# clock.net
KiCad netlist of a schematic drawn in EAGLE
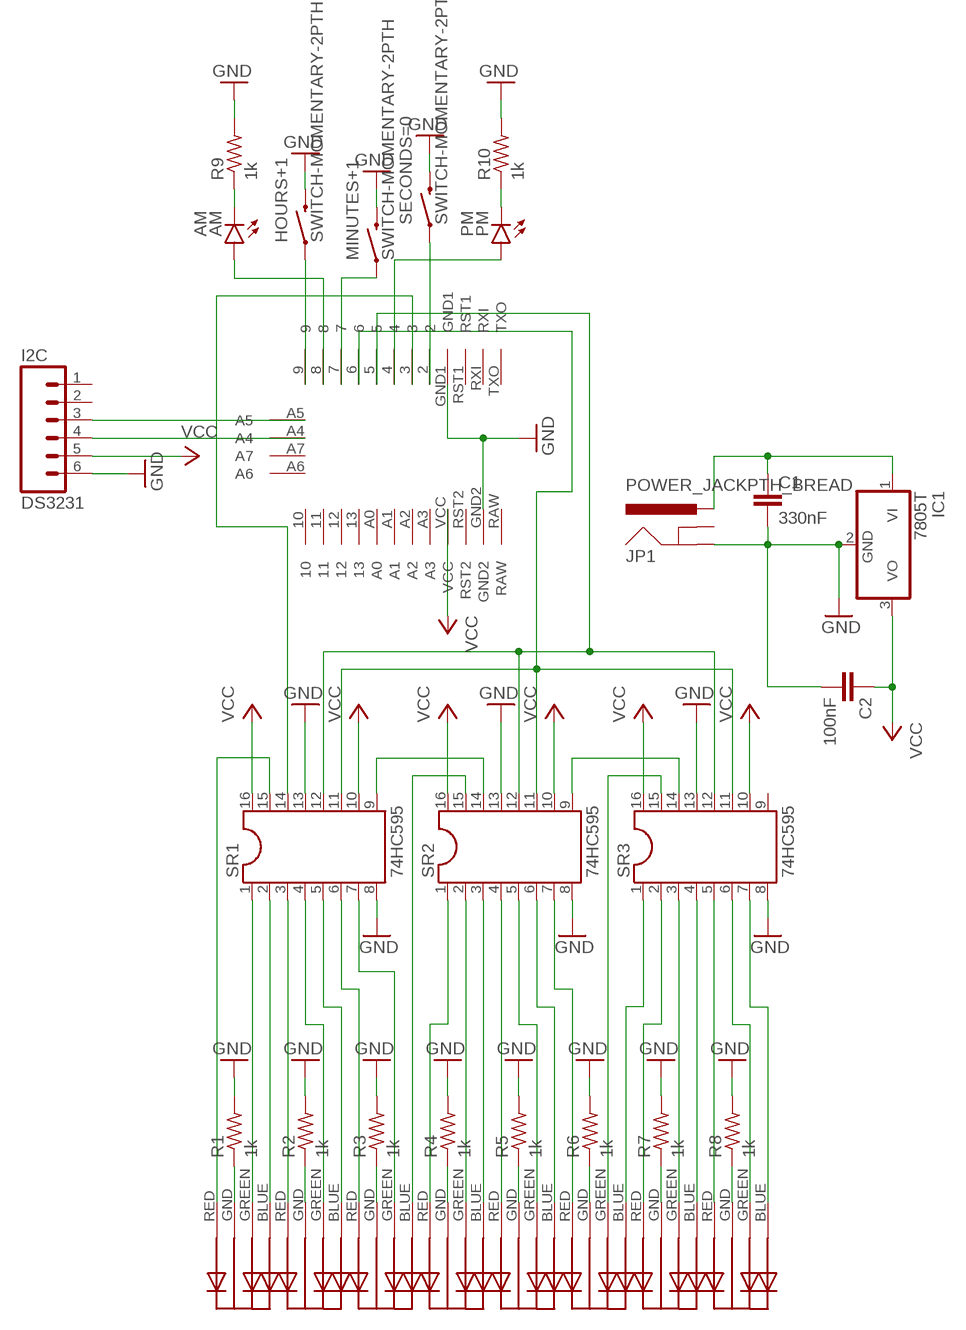
[diagram p0: schematic, sheet 1]

(export (version "E")
  (design (tool "Eeschema 10.0.6"))
  (components
    (comp (ref "AM")
      (value "AM")
      (footprint "eagle-import:LED5MM")
      (libsource (lib "eagle-import") (part "LED5MM"))
    )
    (comp (ref "C1")
      (value "330nF")
      (footprint "eagle-import:CAP-PTH-5MM")
      (libsource (lib "eagle-import") (part "CAPPTH1"))
    )
    (comp (ref "C2")
      (value "100nF")
      (footprint "eagle-import:CAP-PTH-5MM")
      (libsource (lib "eagle-import") (part "CAPPTH1"))
    )
    (comp (ref "DS3231")
      (value "I2C")
      (footprint "eagle-import:1X06_LOCK")
      (libsource (lib "eagle-import") (part "M06LOCK"))
    )
    (comp (ref "HOURS+1")
      (value "SWITCH-MOMENTARY-2PTH")
      (footprint "eagle-import:TACTILE-PTH")
      (libsource (lib "eagle-import") (part "SWITCH-MOMENTARY-2PTH"))
    )
    (comp (ref "IC1")
      (value "7805T")
      (footprint "eagle-import:TO220V")
      (libsource (lib "eagle-import") (part "78TV05"))
    )
    (comp (ref "JP1")
      (value "POWER_JACKPTH_BREAD")
      (footprint "eagle-import:POWER_JACK_PTH_BREAD")
      (libsource (lib "eagle-import") (part "POWER_JACKPTH_BREAD"))
    )
    (comp (ref "MINUTES+1")
      (value "SWITCH-MOMENTARY-2PTH")
      (footprint "eagle-import:TACTILE-PTH")
      (libsource (lib "eagle-import") (part "SWITCH-MOMENTARY-2PTH"))
    )
    (comp (ref "PM")
      (value "PM")
      (footprint "eagle-import:LED5MM")
      (libsource (lib "eagle-import") (part "LED5MM"))
    )
    (comp (ref "R1")
      (value "1k")
      (footprint "eagle-import:0207_10")
      (libsource (lib "eagle-import") (part "R-US_0207/10"))
    )
    (comp (ref "R2")
      (value "1k")
      (footprint "eagle-import:0207_10")
      (libsource (lib "eagle-import") (part "R-US_0207/10"))
    )
    (comp (ref "R3")
      (value "1k")
      (footprint "eagle-import:0207_10")
      (libsource (lib "eagle-import") (part "R-US_0207/10"))
    )
    (comp (ref "R4")
      (value "1k")
      (footprint "eagle-import:0207_10")
      (libsource (lib "eagle-import") (part "R-US_0207/10"))
    )
    (comp (ref "R5")
      (value "1k")
      (footprint "eagle-import:0207_10")
      (libsource (lib "eagle-import") (part "R-US_0207/10"))
    )
    (comp (ref "R6")
      (value "1k")
      (footprint "eagle-import:0207_10")
      (libsource (lib "eagle-import") (part "R-US_0207/10"))
    )
    (comp (ref "R7")
      (value "1k")
      (footprint "eagle-import:0207_10")
      (libsource (lib "eagle-import") (part "R-US_0207/10"))
    )
    (comp (ref "R8")
      (value "1k")
      (footprint "eagle-import:0207_10")
      (libsource (lib "eagle-import") (part "R-US_0207/10"))
    )
    (comp (ref "R9")
      (value "1k")
      (footprint "eagle-import:0207_10")
      (libsource (lib "eagle-import") (part "R-US_0207/10"))
    )
    (comp (ref "R10")
      (value "1k")
      (footprint "eagle-import:0207_10")
      (libsource (lib "eagle-import") (part "R-US_0207/10"))
    )
    (comp (ref "SECONDS=0")
      (value "SWITCH-MOMENTARY-2PTH")
      (footprint "eagle-import:TACTILE-PTH")
      (libsource (lib "eagle-import") (part "SWITCH-MOMENTARY-2PTH"))
    )
    (comp (ref "SR1")
      (value "74HC595")
      (footprint "eagle-import:SOCKET-16")
      (libsource (lib "eagle-import") (part "DIL16S"))
    )
    (comp (ref "SR2")
      (value "74HC595")
      (footprint "eagle-import:SOCKET-16")
      (libsource (lib "eagle-import") (part "DIL16S"))
    )
    (comp (ref "SR3")
      (value "74HC595")
      (footprint "eagle-import:SOCKET-16")
      (libsource (lib "eagle-import") (part "DIL16S"))
    )
    (comp (ref "U$1")
      (value "PRO-MINI")
      (footprint "eagle-import:PRO-MINI")
      (libsource (lib "eagle-import") (part "PRO-MINI"))
    )
    (comp (ref "U$2")
      (value "RGB_LED_COM_CATH")
      (footprint "eagle-import:RGB_LED_COM_CATH")
      (libsource (lib "eagle-import") (part "RGB_LED_COM_CATH"))
    )
    (comp (ref "U$3")
      (value "RGB_LED_COM_CATH")
      (footprint "eagle-import:RGB_LED_COM_CATH")
      (libsource (lib "eagle-import") (part "RGB_LED_COM_CATH"))
    )
    (comp (ref "U$4")
      (value "RGB_LED_COM_CATH")
      (footprint "eagle-import:RGB_LED_COM_CATH")
      (libsource (lib "eagle-import") (part "RGB_LED_COM_CATH"))
    )
    (comp (ref "U$5")
      (value "RGB_LED_COM_CATH")
      (footprint "eagle-import:RGB_LED_COM_CATH")
      (libsource (lib "eagle-import") (part "RGB_LED_COM_CATH"))
    )
    (comp (ref "U$6")
      (value "RGB_LED_COM_CATH")
      (footprint "eagle-import:RGB_LED_COM_CATH")
      (libsource (lib "eagle-import") (part "RGB_LED_COM_CATH"))
    )
    (comp (ref "U$7")
      (value "RGB_LED_COM_CATH")
      (footprint "eagle-import:RGB_LED_COM_CATH")
      (libsource (lib "eagle-import") (part "RGB_LED_COM_CATH"))
    )
    (comp (ref "U$8")
      (value "RGB_LED_COM_CATH")
      (footprint "eagle-import:RGB_LED_COM_CATH")
      (libsource (lib "eagle-import") (part "RGB_LED_COM_CATH"))
    )
    (comp (ref "U$9")
      (value "RGB_LED_COM_CATH")
      (footprint "eagle-import:RGB_LED_COM_CATH")
      (libsource (lib "eagle-import") (part "RGB_LED_COM_CATH"))
    )
  )
  (nets
    (net (code "1") (name "GND") (class "Default")
      (node (ref "C1") (pin "2") (pinfunction "2_2") (pintype "passive"))
      (node (ref "C2") (pin "2") (pinfunction "2_2") (pintype "passive"))
      (node (ref "DS3231") (pin "6") (pinfunction "6_6") (pintype "passive"))
      (node (ref "HOURS+1") (pin "3") (pinfunction "2_3") (pintype "passive"))
      (node (ref "IC1") (pin "2") (pinfunction "GND_2") (pintype "passive"))
      (node (ref "JP1") (pin "GND") (pinfunction "GND_GND") (pintype "bidirectional"))
      (node (ref "MINUTES+1") (pin "3") (pinfunction "2_3") (pintype "passive"))
      (node (ref "R1") (pin "2") (pinfunction "2_2") (pintype "passive"))
      (node (ref "R10") (pin "2") (pinfunction "2_2") (pintype "passive"))
      (node (ref "R2") (pin "2") (pinfunction "2_2") (pintype "passive"))
      (node (ref "R3") (pin "2") (pinfunction "2_2") (pintype "passive"))
      (node (ref "R4") (pin "2") (pinfunction "2_2") (pintype "passive"))
      (node (ref "R5") (pin "2") (pinfunction "2_2") (pintype "passive"))
      (node (ref "R6") (pin "2") (pinfunction "2_2") (pintype "passive"))
      (node (ref "R7") (pin "2") (pinfunction "2_2") (pintype "passive"))
      (node (ref "R8") (pin "2") (pinfunction "2_2") (pintype "passive"))
      (node (ref "R9") (pin "2") (pinfunction "2_2") (pintype "passive"))
      (node (ref "SECONDS=0") (pin "3") (pinfunction "2_3") (pintype "passive"))
      (node (ref "SR1") (pin "13") (pinfunction "13_13") (pintype "passive"))
      (node (ref "SR1") (pin "8") (pinfunction "8_8") (pintype "passive"))
      (node (ref "SR2") (pin "13") (pinfunction "13_13") (pintype "passive"))
      (node (ref "SR2") (pin "8") (pinfunction "8_8") (pintype "passive"))
      (node (ref "SR3") (pin "13") (pinfunction "13_13") (pintype "passive"))
      (node (ref "SR3") (pin "8") (pinfunction "8_8") (pintype "passive"))
      (node (ref "U$1") (pin "GND1") (pinfunction "GND1_GND1") (pintype "bidirectional"))
      (node (ref "U$1") (pin "GND2") (pinfunction "GND2_GND2") (pintype "bidirectional"))
    )
    (net (code "2") (name "Net-(AM-C)") (class "Default")
      (node (ref "AM") (pin "K") (pinfunction "C_K") (pintype "passive"))
      (node (ref "R9") (pin "1") (pinfunction "1_1") (pintype "passive"))
    )
    (net (code "3") (name "Net-(AM-PadA)") (class "Default")
      (node (ref "AM") (pin "A") (pinfunction "A_A") (pintype "passive"))
      (node (ref "U$1") (pin "8") (pinfunction "8_8") (pintype "bidirectional"))
    )
    (net (code "4") (name "Net-(DS3231-Pad3)") (class "Default")
      (node (ref "DS3231") (pin "3") (pinfunction "3_3") (pintype "passive"))
      (node (ref "U$1") (pin "A5") (pinfunction "A5_A5") (pintype "bidirectional"))
    )
    (net (code "5") (name "Net-(DS3231-Pad4)") (class "Default")
      (node (ref "DS3231") (pin "4") (pinfunction "4_4") (pintype "passive"))
      (node (ref "U$1") (pin "A4") (pinfunction "A4_A4") (pintype "bidirectional"))
    )
    (net (code "6") (name "Net-(HOURS+1-Pad1)") (class "Default")
      (node (ref "HOURS+1") (pin "1") (pinfunction "1_1") (pintype "passive"))
      (node (ref "U$1") (pin "9") (pinfunction "9_9") (pintype "bidirectional"))
    )
    (net (code "7") (name "Net-(IC1-VI)") (class "Default")
      (node (ref "C1") (pin "1") (pinfunction "1_1") (pintype "passive"))
      (node (ref "IC1") (pin "1") (pinfunction "VI_1") (pintype "input"))
      (node (ref "JP1") (pin "PWR") (pinfunction "PWR_PWR") (pintype "bidirectional"))
    )
    (net (code "8") (name "Net-(MINUTES+1-Pad1)") (class "Default")
      (node (ref "MINUTES+1") (pin "1") (pinfunction "1_1") (pintype "passive"))
      (node (ref "U$1") (pin "7") (pinfunction "7_7") (pintype "bidirectional"))
    )
    (net (code "9") (name "Net-(PM-C)") (class "Default")
      (node (ref "PM") (pin "K") (pinfunction "C_K") (pintype "passive"))
      (node (ref "R10") (pin "1") (pinfunction "1_1") (pintype "passive"))
    )
    (net (code "10") (name "Net-(PM-PadA)") (class "Default")
      (node (ref "PM") (pin "A") (pinfunction "A_A") (pintype "passive"))
      (node (ref "U$1") (pin "4") (pinfunction "4_4") (pintype "bidirectional"))
    )
    (net (code "11") (name "Net-(R1-Pad1)") (class "Default")
      (node (ref "R1") (pin "1") (pinfunction "1_1") (pintype "passive"))
      (node (ref "U$4") (pin "GND") (pinfunction "GND_GND") (pintype "bidirectional"))
    )
    (net (code "12") (name "Net-(R2-Pad1)") (class "Default")
      (node (ref "R2") (pin "1") (pinfunction "1_1") (pintype "passive"))
      (node (ref "U$3") (pin "GND") (pinfunction "GND_GND") (pintype "bidirectional"))
    )
    (net (code "13") (name "Net-(R3-Pad1)") (class "Default")
      (node (ref "R3") (pin "1") (pinfunction "1_1") (pintype "passive"))
      (node (ref "U$2") (pin "GND") (pinfunction "GND_GND") (pintype "bidirectional"))
    )
    (net (code "14") (name "Net-(R4-Pad1)") (class "Default")
      (node (ref "R4") (pin "1") (pinfunction "1_1") (pintype "passive"))
      (node (ref "U$5") (pin "GND") (pinfunction "GND_GND") (pintype "bidirectional"))
    )
    (net (code "15") (name "Net-(R5-Pad1)") (class "Default")
      (node (ref "R5") (pin "1") (pinfunction "1_1") (pintype "passive"))
      (node (ref "U$6") (pin "GND") (pinfunction "GND_GND") (pintype "bidirectional"))
    )
    (net (code "16") (name "Net-(R6-Pad1)") (class "Default")
      (node (ref "R6") (pin "1") (pinfunction "1_1") (pintype "passive"))
      (node (ref "U$7") (pin "GND") (pinfunction "GND_GND") (pintype "bidirectional"))
    )
    (net (code "17") (name "Net-(R7-Pad1)") (class "Default")
      (node (ref "R7") (pin "1") (pinfunction "1_1") (pintype "passive"))
      (node (ref "U$8") (pin "GND") (pinfunction "GND_GND") (pintype "bidirectional"))
    )
    (net (code "18") (name "Net-(R8-Pad1)") (class "Default")
      (node (ref "R8") (pin "1") (pinfunction "1_1") (pintype "passive"))
      (node (ref "U$9") (pin "GND") (pinfunction "GND_GND") (pintype "bidirectional"))
    )
    (net (code "19") (name "Net-(SECONDS=0-Pad1)") (class "Default")
      (node (ref "SECONDS=0") (pin "1") (pinfunction "1_1") (pintype "passive"))
      (node (ref "U$1") (pin "2") (pinfunction "2_2") (pintype "bidirectional"))
    )
    (net (code "20") (name "Net-(SR1-Pad1)") (class "Default")
      (node (ref "SR1") (pin "1") (pinfunction "1_1") (pintype "passive"))
      (node (ref "U$4") (pin "GREEN") (pinfunction "GREEN_GREEN") (pintype "bidirectional"))
    )
    (net (code "21") (name "Net-(SR1-Pad2)") (class "Default")
      (node (ref "SR1") (pin "2") (pinfunction "2_2") (pintype "passive"))
      (node (ref "U$4") (pin "BLUE") (pinfunction "BLUE_BLUE") (pintype "bidirectional"))
    )
    (net (code "22") (name "Net-(SR1-Pad3)") (class "Default")
      (node (ref "SR1") (pin "3") (pinfunction "3_3") (pintype "passive"))
      (node (ref "U$3") (pin "RED") (pinfunction "RED_RED") (pintype "bidirectional"))
    )
    (net (code "23") (name "Net-(SR1-Pad4)") (class "Default")
      (node (ref "SR1") (pin "4") (pinfunction "4_4") (pintype "passive"))
      (node (ref "U$3") (pin "GREEN") (pinfunction "GREEN_GREEN") (pintype "bidirectional"))
    )
    (net (code "24") (name "Net-(SR1-Pad5)") (class "Default")
      (node (ref "SR1") (pin "5") (pinfunction "5_5") (pintype "passive"))
      (node (ref "U$3") (pin "BLUE") (pinfunction "BLUE_BLUE") (pintype "bidirectional"))
    )
    (net (code "25") (name "Net-(SR1-Pad6)") (class "Default")
      (node (ref "SR1") (pin "6") (pinfunction "6_6") (pintype "passive"))
      (node (ref "U$2") (pin "RED") (pinfunction "RED_RED") (pintype "bidirectional"))
    )
    (net (code "26") (name "Net-(SR1-Pad7)") (class "Default")
      (node (ref "SR1") (pin "7") (pinfunction "7_7") (pintype "passive"))
      (node (ref "U$2") (pin "GREEN") (pinfunction "GREEN_GREEN") (pintype "bidirectional"))
    )
    (net (code "27") (name "Net-(SR1-Pad9)") (class "Default")
      (node (ref "SR1") (pin "9") (pinfunction "9_9") (pintype "passive"))
      (node (ref "SR2") (pin "14") (pinfunction "14_14") (pintype "passive"))
    )
    (net (code "28") (name "Net-(SR1-Pad11)") (class "Default")
      (node (ref "SR1") (pin "11") (pinfunction "11_11") (pintype "passive"))
      (node (ref "SR2") (pin "11") (pinfunction "11_11") (pintype "passive"))
      (node (ref "SR3") (pin "11") (pinfunction "11_11") (pintype "passive"))
      (node (ref "U$1") (pin "6") (pinfunction "6_6") (pintype "bidirectional"))
    )
    (net (code "29") (name "Net-(SR1-Pad12)") (class "Default")
      (node (ref "SR1") (pin "12") (pinfunction "12_12") (pintype "passive"))
      (node (ref "SR2") (pin "12") (pinfunction "12_12") (pintype "passive"))
      (node (ref "SR3") (pin "12") (pinfunction "12_12") (pintype "passive"))
      (node (ref "U$1") (pin "5") (pinfunction "5_5") (pintype "bidirectional"))
    )
    (net (code "30") (name "Net-(SR1-Pad14)") (class "Default")
      (node (ref "SR1") (pin "14") (pinfunction "14_14") (pintype "passive"))
      (node (ref "U$1") (pin "3") (pinfunction "3_3") (pintype "bidirectional"))
    )
    (net (code "31") (name "Net-(SR1-Pad15)") (class "Default")
      (node (ref "SR1") (pin "15") (pinfunction "15_15") (pintype "passive"))
      (node (ref "U$4") (pin "RED") (pinfunction "RED_RED") (pintype "bidirectional"))
    )
    (net (code "32") (name "Net-(SR2-Pad1)") (class "Default")
      (node (ref "SR2") (pin "1") (pinfunction "1_1") (pintype "passive"))
      (node (ref "U$5") (pin "RED") (pinfunction "RED_RED") (pintype "bidirectional"))
    )
    (net (code "33") (name "Net-(SR2-Pad2)") (class "Default")
      (node (ref "SR2") (pin "2") (pinfunction "2_2") (pintype "passive"))
      (node (ref "U$5") (pin "GREEN") (pinfunction "GREEN_GREEN") (pintype "bidirectional"))
    )
    (net (code "34") (name "Net-(SR2-Pad3)") (class "Default")
      (node (ref "SR2") (pin "3") (pinfunction "3_3") (pintype "passive"))
      (node (ref "U$5") (pin "BLUE") (pinfunction "BLUE_BLUE") (pintype "bidirectional"))
    )
    (net (code "35") (name "Net-(SR2-Pad4)") (class "Default")
      (node (ref "SR2") (pin "4") (pinfunction "4_4") (pintype "passive"))
      (node (ref "U$6") (pin "RED") (pinfunction "RED_RED") (pintype "bidirectional"))
    )
    (net (code "36") (name "Net-(SR2-Pad5)") (class "Default")
      (node (ref "SR2") (pin "5") (pinfunction "5_5") (pintype "passive"))
      (node (ref "U$6") (pin "GREEN") (pinfunction "GREEN_GREEN") (pintype "bidirectional"))
    )
    (net (code "37") (name "Net-(SR2-Pad6)") (class "Default")
      (node (ref "SR2") (pin "6") (pinfunction "6_6") (pintype "passive"))
      (node (ref "U$6") (pin "BLUE") (pinfunction "BLUE_BLUE") (pintype "bidirectional"))
    )
    (net (code "38") (name "Net-(SR2-Pad7)") (class "Default")
      (node (ref "SR2") (pin "7") (pinfunction "7_7") (pintype "passive"))
      (node (ref "U$7") (pin "RED") (pinfunction "RED_RED") (pintype "bidirectional"))
    )
    (net (code "39") (name "Net-(SR2-Pad9)") (class "Default")
      (node (ref "SR2") (pin "9") (pinfunction "9_9") (pintype "passive"))
      (node (ref "SR3") (pin "14") (pinfunction "14_14") (pintype "passive"))
    )
    (net (code "40") (name "Net-(SR2-Pad15)") (class "Default")
      (node (ref "SR2") (pin "15") (pinfunction "15_15") (pintype "passive"))
      (node (ref "U$2") (pin "BLUE") (pinfunction "BLUE_BLUE") (pintype "bidirectional"))
    )
    (net (code "41") (name "Net-(SR3-Pad1)") (class "Default")
      (node (ref "SR3") (pin "1") (pinfunction "1_1") (pintype "passive"))
      (node (ref "U$7") (pin "BLUE") (pinfunction "BLUE_BLUE") (pintype "bidirectional"))
    )
    (net (code "42") (name "Net-(SR3-Pad2)") (class "Default")
      (node (ref "SR3") (pin "2") (pinfunction "2_2") (pintype "passive"))
      (node (ref "U$8") (pin "RED") (pinfunction "RED_RED") (pintype "bidirectional"))
    )
    (net (code "43") (name "Net-(SR3-Pad3)") (class "Default")
      (node (ref "SR3") (pin "3") (pinfunction "3_3") (pintype "passive"))
      (node (ref "U$8") (pin "GREEN") (pinfunction "GREEN_GREEN") (pintype "bidirectional"))
    )
    (net (code "44") (name "Net-(SR3-Pad4)") (class "Default")
      (node (ref "SR3") (pin "4") (pinfunction "4_4") (pintype "passive"))
      (node (ref "U$8") (pin "BLUE") (pinfunction "BLUE_BLUE") (pintype "bidirectional"))
    )
    (net (code "45") (name "Net-(SR3-Pad5)") (class "Default")
      (node (ref "SR3") (pin "5") (pinfunction "5_5") (pintype "passive"))
      (node (ref "U$9") (pin "RED") (pinfunction "RED_RED") (pintype "bidirectional"))
    )
    (net (code "46") (name "Net-(SR3-Pad6)") (class "Default")
      (node (ref "SR3") (pin "6") (pinfunction "6_6") (pintype "passive"))
      (node (ref "U$9") (pin "GREEN") (pinfunction "GREEN_GREEN") (pintype "bidirectional"))
    )
    (net (code "47") (name "Net-(SR3-Pad7)") (class "Default")
      (node (ref "SR3") (pin "7") (pinfunction "7_7") (pintype "passive"))
      (node (ref "U$9") (pin "BLUE") (pinfunction "BLUE_BLUE") (pintype "bidirectional"))
    )
    (net (code "48") (name "Net-(SR3-Pad15)") (class "Default")
      (node (ref "SR3") (pin "15") (pinfunction "15_15") (pintype "passive"))
      (node (ref "U$7") (pin "GREEN") (pinfunction "GREEN_GREEN") (pintype "bidirectional"))
    )
    (net (code "49") (name "VCC") (class "Default")
      (node (ref "C2") (pin "1") (pinfunction "1_1") (pintype "passive"))
      (node (ref "DS3231") (pin "5") (pinfunction "5_5") (pintype "passive"))
      (node (ref "IC1") (pin "3") (pinfunction "VO_3") (pintype "passive"))
      (node (ref "SR1") (pin "10") (pinfunction "10_10") (pintype "passive"))
      (node (ref "SR1") (pin "16") (pinfunction "16_16") (pintype "passive"))
      (node (ref "SR2") (pin "10") (pinfunction "10_10") (pintype "passive"))
      (node (ref "SR2") (pin "16") (pinfunction "16_16") (pintype "passive"))
      (node (ref "SR3") (pin "10") (pinfunction "10_10") (pintype "passive"))
      (node (ref "SR3") (pin "16") (pinfunction "16_16") (pintype "passive"))
      (node (ref "U$1") (pin "VCC") (pinfunction "VCC_VCC") (pintype "bidirectional"))
    )
    (net (code "50") (name "unconnected-(DS3231-Pad1)") (class "Default")
      (node (ref "DS3231") (pin "1") (pinfunction "1_1") (pintype "passive"))
    )
    (net (code "51") (name "unconnected-(DS3231-Pad2)") (class "Default")
      (node (ref "DS3231") (pin "2") (pinfunction "2_2") (pintype "passive"))
    )
    (net (code "52") (name "unconnected-(JP1-PadGNDBREAK)") (class "Default")
      (node (ref "JP1") (pin "GNDBREAK") (pinfunction "GNDBREAK_GNDBREAK") (pintype "bidirectional"))
    )
    (net (code "53") (name "unconnected-(SR3-Pad9)") (class "Default")
      (node (ref "SR3") (pin "9") (pinfunction "9_9") (pintype "passive"))
    )
    (net (code "54") (name "unconnected-(U$1-Pad10)") (class "Default")
      (node (ref "U$1") (pin "10") (pinfunction "10_10") (pintype "bidirectional"))
    )
    (net (code "55") (name "unconnected-(U$1-Pad11)") (class "Default")
      (node (ref "U$1") (pin "11") (pinfunction "11_11") (pintype "bidirectional"))
    )
    (net (code "56") (name "unconnected-(U$1-Pad12)") (class "Default")
      (node (ref "U$1") (pin "12") (pinfunction "12_12") (pintype "bidirectional"))
    )
    (net (code "57") (name "unconnected-(U$1-Pad13)") (class "Default")
      (node (ref "U$1") (pin "13") (pinfunction "13_13") (pintype "bidirectional"))
    )
    (net (code "58") (name "unconnected-(U$1-PadA0)") (class "Default")
      (node (ref "U$1") (pin "A0") (pinfunction "A0_A0") (pintype "bidirectional"))
    )
    (net (code "59") (name "unconnected-(U$1-PadA1)") (class "Default")
      (node (ref "U$1") (pin "A1") (pinfunction "A1_A1") (pintype "bidirectional"))
    )
    (net (code "60") (name "unconnected-(U$1-PadA2)") (class "Default")
      (node (ref "U$1") (pin "A2") (pinfunction "A2_A2") (pintype "bidirectional"))
    )
    (net (code "61") (name "unconnected-(U$1-PadA3)") (class "Default")
      (node (ref "U$1") (pin "A3") (pinfunction "A3_A3") (pintype "bidirectional"))
    )
    (net (code "62") (name "unconnected-(U$1-PadA6)") (class "Default")
      (node (ref "U$1") (pin "A6") (pinfunction "A6_A6") (pintype "bidirectional"))
    )
    (net (code "63") (name "unconnected-(U$1-PadA7)") (class "Default")
      (node (ref "U$1") (pin "A7") (pinfunction "A7_A7") (pintype "bidirectional"))
    )
    (net (code "64") (name "unconnected-(U$1-PadRAW)") (class "Default")
      (node (ref "U$1") (pin "RAW") (pinfunction "RAW_RAW") (pintype "bidirectional"))
    )
    (net (code "65") (name "unconnected-(U$1-PadRST1)") (class "Default")
      (node (ref "U$1") (pin "RST1") (pinfunction "RST1_RST1") (pintype "bidirectional"))
    )
    (net (code "66") (name "unconnected-(U$1-PadRST2)") (class "Default")
      (node (ref "U$1") (pin "RST2") (pinfunction "RST2_RST2") (pintype "bidirectional"))
    )
    (net (code "67") (name "unconnected-(U$1-PadRXI)") (class "Default")
      (node (ref "U$1") (pin "RXI") (pinfunction "RXI_RXI") (pintype "bidirectional"))
    )
    (net (code "68") (name "unconnected-(U$1-PadTXO)") (class "Default")
      (node (ref "U$1") (pin "TXO") (pinfunction "TXO_TXO") (pintype "bidirectional"))
    )
  )
)
